# si4463.net
KiCad netlist of a schematic drawn in Altium Designer
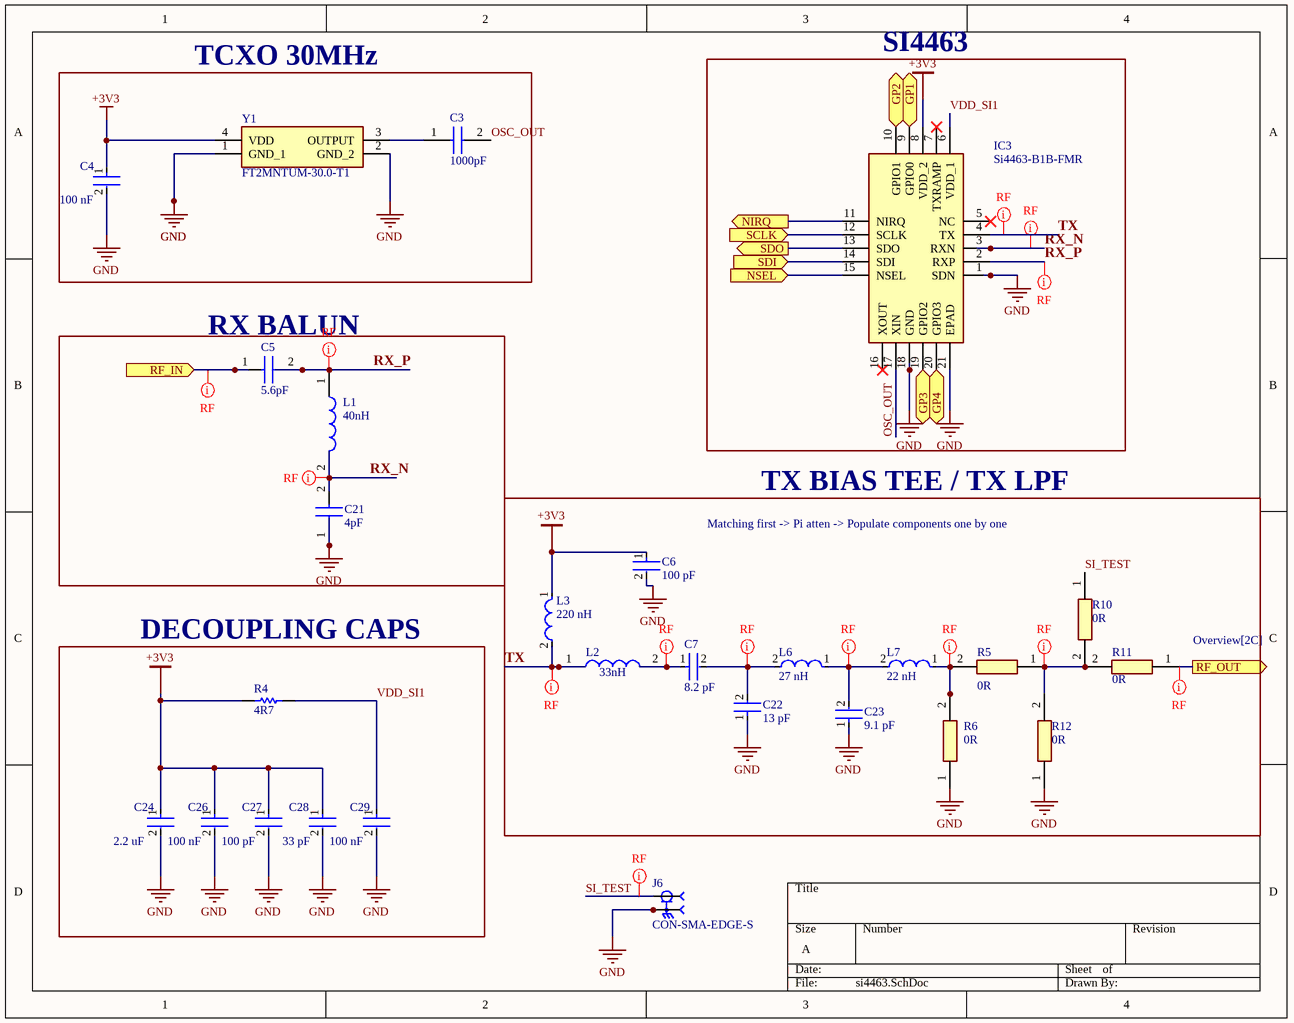
[diagram p0: si4463.SchDoc]

(export (version "E")
  (design (tool "Eeschema 10.0.6"))
  (components
    (comp (ref "C3")
      (value "1000pF")
      (footprint "SamacSys:C0402")
      (description "C0402C102K5RAC-TU")
      (libsource (lib "*") (part "C0402C102K5RAC-TU"))
    )
    (comp (ref "C4")
      (value "100 nF")
      (footprint "FP-GCM155-0_05-IPC_C")
      (description "Ceramic Capacitor for Automotive 100nF ±10% 16VDC X7R 0402 Paper T/R Name: GCM155R71C104KA55D")
      (fields (field (name "VOLTAGE") "16V") (field (name "TOLERANCE") "10%"))
      (libsource (lib "Altium Content Vault") (part "02cd4be3c70576c341d710602a673aa"))
    )
    (comp (ref "C5")
      (value "5.6pF")
      (footprint "SamacSys:CAPC1005X55N")
      (description "GJM1555C1H5R6BB01D")
      (fields (field (name "MOUSER PART NUMBER") "81-GJM1555C1H5R6BB1D"))
      (libsource (lib "*") (part "GJM1555C1H5R6BB01D"))
    )
    (comp (ref "C6")
      (value "100 pF")
      (footprint "FP-GQM187-0_15-MFG")
      (description "Ceramic Capacitor 100pF ±5% 250VDC C0G 0603 Paper T/R Name: GQM1875C2E101JB12D")
      (fields (field (name "TOLERANCE") "5%"))
      (libsource (lib "Altium Content Vault") (part "02cd4be3c70576c341d710602a673aa"))
    )
    (comp (ref "C7")
      (value "8.2 pF")
      (footprint "FP-GJM155-0_05-MFG")
      (description "Multi-Layer Ceramic Capacitor 8.2pF C0G  ±0.05pF 0402 Paper T/R")
      (libsource (lib "Altium Content Vault") (part "02cd4be3c70576c341d710602a673aa"))
    )
    (comp (ref "C21")
      (value "4pF")
      (footprint "SamacSys:CAPC1005X55N")
      (description "GJM1555C1H4R0BB01D")
      (fields (field (name "MOUSER PART NUMBER") "81-GJM1555C1H4R0BB01"))
      (libsource (lib "*") (part "GJM1555C1H4R0BB01D"))
    )
    (comp (ref "C22")
      (value "13 pF")
      (footprint "FP-GJM155-0_05-IPC_B")
      (description "Multi-Layer Ceramic Capacitor 13pF C0G  ±2% 0402 Paper T/R Name: GJM1555C1H130GB01D")
      (fields (field (name "TOLERANCE") "2%"))
      (libsource (lib "Altium Content Vault") (part "02cd4be3c70576c341d710602a673aa"))
    )
    (comp (ref "C23")
      (value "9.1 pF")
      (footprint "FP-GJM155-0_05-IPC_B")
      (description "Multi-Layer Ceramic Capacitor 9.1pF C0G  ±0.1pF 0402 Paper T/R Name: GJM1555C1H9R1BB01D")
      (libsource (lib "Altium Content Vault") (part "02cd4be3c70576c341d710602a673aa"))
    )
    (comp (ref "C24")
      (value "2.2 uF")
      (footprint "FP-GRM155-0_2-IPC_A")
      (fields (field (name "TOLERANCE") "10%"))
      (libsource (lib "Altium Content Vault") (part "b4654b650e69147ec39a6b967a45e02"))
    )
    (comp (ref "C26")
      (value "100 nF")
      (footprint "FP-GCM155-0_05-IPC_C")
      (description "Ceramic Capacitor for Automotive 100nF ±10% 16VDC X7R 0402 Paper T/R Name: GCM155R71C104KA55D")
      (fields (field (name "VOLTAGE") "16V") (field (name "TOLERANCE") "10%"))
      (libsource (lib "Altium Content Vault") (part "02cd4be3c70576c341d710602a673aa"))
    )
    (comp (ref "C27")
      (value "100 pF")
      (footprint "FP-GQM187-0_15-MFG")
      (description "Ceramic Capacitor 100pF ±5% 250VDC C0G 0603 Paper T/R Name: GQM1875C2E101JB12D")
      (fields (field (name "TOLERANCE") "5%"))
      (libsource (lib "Altium Content Vault") (part "02cd4be3c70576c341d710602a673aa"))
    )
    (comp (ref "C28")
      (value "33 pF")
      (footprint "FP-GJM155-0_05-MFG")
      (description "Multi-Layer Ceramic Capacitor 33pF C0G  ±5% 0402 Paper T/R Name: GJM1555C1H330JB01D")
      (fields (field (name "TOLERANCE") "5%"))
      (libsource (lib "Altium Content Vault") (part "02cd4be3c70576c341d710602a673aa"))
    )
    (comp (ref "C29")
      (value "100 nF")
      (footprint "FP-GCM155-0_05-IPC_C")
      (description "Ceramic Capacitor for Automotive 100nF ±10% 16VDC X7R 0402 Paper T/R Name: GCM155R71C104KA55D")
      (fields (field (name "VOLTAGE") "16V") (field (name "TOLERANCE") "10%"))
      (libsource (lib "Altium Content Vault") (part "02cd4be3c70576c341d710602a673aa"))
    )
    (comp (ref "IC3")
      (value "Si4463-B1B-FMR")
      (footprint "SamacSys:QFN50P400X400X90-21N-D")
      (description "Integrated Circuit")
      (fields
        (field (name "MOUSER PART NUMBER") "634-SI4463-B1B-FMR")
        (field (name "ARROW PART NUMBER") "SI4463-B1B-FMR")
      )
      (libsource (lib "*") (part "Si4463-B1B-FMR"))
    )
    (comp (ref "J6")
      (value "CON-SMA-EDGE-S")
      (footprint "RFSOLUTIONS_CON-SMA-EDGE-S")
      (description "SMA Connector Jack, Female Socket - Board Edge, End Launch Solder")
      (fields (field (name "MF") "RF Solutions") (field (name "DIGI-KEY_PART_NUMBER") "CON-SMA-EDGE-S-ND"))
      (libsource (lib "Americas- Calgary to Space- Calgary University") (part "CON-SMA-EDGE-S"))
    )
    (comp (ref "L1")
      (value "40nH")
      (footprint "SamacSys:LQW15CNR20J00B")
      (description "LQW15AN40NJ00D")
      (fields (field (name "MOUSER PART NUMBER") "81-LQW15AN40NJ00D"))
      (libsource (lib "*") (part "LQW15AN40NJ00D"))
    )
    (comp (ref "L2")
      (value "33nH")
      (footprint "SamacSys:LQW15CNR20J00B")
      (description "LQW15AN33NJ00D")
      (fields (field (name "MOUSER PART NUMBER") "81-LQW15AN33NJ00D"))
      (libsource (lib "*") (part "LQW15AN33NJ00D"))
    )
    (comp (ref "L3")
      (value "220 nH")
      (footprint "FP-LQW18AN_80-MFG")
      (description "Wire Wound RF Inductor for Automotive 220nH ±5% 280mA 2.08Ω 0603 (1608) Name: LQW18ANR22J8ZD")
      (libsource (lib "Altium Content Vault") (part "725321dda6339637d4d059423bc1c3c"))
    )
    (comp (ref "L6")
      (value "27 nH")
      (footprint "FP-LQW15AN_00-W0_5-0_1-MFG")
      (description "Wire Wound RF Inductor 27nH ±3% 280mA 0.52Ω 0402 (1005) Name: LQW15AN27NH00D")
      (fields (field (name "TOLERANCE") "3%"))
      (libsource (lib "Altium Content Vault") (part "725321dda6339637d4d059423bc1c3c"))
    )
    (comp (ref "L7")
      (value "22 nH")
      (footprint "FP-LQW15AN_00-W0_6-0_1-MFG")
      (description "Wire Wound RF Inductor 22nH ±3% 310mA 0.3Ω 0402 (1005) Name: LQW15AN22NH00D")
      (fields (field (name "TOLERANCE") "3%"))
      (libsource (lib "Altium Content Vault") (part "725321dda6339637d4d059423bc1c3c"))
    )
    (comp (ref "R4")
      (value "4R7")
      (footprint "RESC3216X65X100LL20T15")
      (description "Name: RL1632R-4R70-F")
      (fields (field (name "MANUFACTURER") "Susumu") (field (name "PART NUMBER") "RL1632R-4R70-F"))
      (libsource (lib "Altium Content Vault") (part "RES"))
    )
    (comp (ref "R5")
      (value "0R")
      (footprint "SamacSys:RESC1608X55N")
      (description "RC0603JR-070RL")
      (fields (field (name "MOUSER PART NUMBER") "603-RC0603JR-070RL"))
      (libsource (lib "*") (part "RC0603JR-070RL"))
    )
    (comp (ref "R6")
      (value "0R")
      (footprint "SamacSys:RESC1608X55N")
      (description "RC0603JR-070RL")
      (fields (field (name "MOUSER PART NUMBER") "603-RC0603JR-070RL"))
      (libsource (lib "") (part "RC0603JR-070RL_1"))
    )
    (comp (ref "R10")
      (value "0R")
      (footprint "SamacSys:RESC1005X40N")
      (description "RC0402JR-070RL")
      (fields (field (name "MOUSER PART NUMBER") "603-RC0402JR-070RL"))
      (libsource (lib "*") (part "RC0402JR-070RL"))
    )
    (comp (ref "R11")
      (value "0R")
      (footprint "SamacSys:RESC1608X55N")
      (description "RC0603JR-070RL")
      (fields (field (name "MOUSER PART NUMBER") "603-RC0603JR-070RL"))
      (libsource (lib "*") (part "RC0603JR-070RL"))
    )
    (comp (ref "R12")
      (value "0R")
      (footprint "SamacSys:RESC1608X55N")
      (description "RC0603JR-070RL")
      (fields (field (name "MOUSER PART NUMBER") "603-RC0603JR-070RL"))
      (libsource (lib "") (part "RC0603JR-070RL_1"))
    )
    (comp (ref "Y1")
      (value "FT2MNTUM-30.0-T1")
      (footprint "SamacSys:FT2MNTUM300T1")
      (description "Crystal or Oscillator")
      (fields (field (name "MOUSER PART NUMBER") "815-FT2MNTUM-30.0-T1"))
      (libsource (lib "*") (part "FT2MNTUM-30.0-T1"))
    )
  )
  (nets
    (net (code "1") (name "+3V3") (class "Default")
      (node (ref "C24") (pin "1") (pinfunction "1_1") (pintype "passive"))
      (node (ref "C26") (pin "1") (pinfunction "1_1") (pintype "passive"))
      (node (ref "C27") (pin "1") (pinfunction "1_1") (pintype "passive"))
      (node (ref "C28") (pin "1") (pinfunction "1_1") (pintype "passive"))
      (node (ref "C4") (pin "1") (pinfunction "1_1") (pintype "passive"))
      (node (ref "C6") (pin "1") (pinfunction "1_1") (pintype "passive"))
      (node (ref "IC3") (pin "8") (pinfunction "VDD_2_8") (pintype "passive"))
      (node (ref "L3") (pin "1") (pinfunction "1_1") (pintype "passive"))
      (node (ref "R4") (pin "1") (pinfunction "1_1") (pintype "passive"))
      (node (ref "Y1") (pin "4") (pinfunction "VDD_4") (pintype "passive"))
    )
    (net (code "2") (name "/GP1") (class "Default")
      (node (ref "IC3") (pin "9") (pinfunction "GPIO0_9") (pintype "passive"))
    )
    (net (code "3") (name "/GP2") (class "Default")
      (node (ref "IC3") (pin "10") (pinfunction "GPIO1_10") (pintype "passive"))
    )
    (net (code "4") (name "/GP3") (class "Default")
      (node (ref "IC3") (pin "19") (pinfunction "GPIO2_19") (pintype "passive"))
    )
    (net (code "5") (name "/GP4") (class "Default")
      (node (ref "IC3") (pin "20") (pinfunction "GPIO3_20") (pintype "passive"))
    )
    (net (code "6") (name "/NIRQ") (class "Default")
      (node (ref "IC3") (pin "11") (pinfunction "NIRQ_11") (pintype "passive"))
    )
    (net (code "7") (name "/NSEL") (class "Default")
      (node (ref "IC3") (pin "15") (pinfunction "NSEL_15") (pintype "passive"))
    )
    (net (code "8") (name "/OSC_OUT") (class "Default")
      (node (ref "C3") (pin "2") (pinfunction "2_2") (pintype "passive"))
      (node (ref "IC3") (pin "17") (pinfunction "XIN_17") (pintype "passive"))
    )
    (net (code "9") (name "/RF_IN") (class "Default")
      (node (ref "C5") (pin "1") (pinfunction "1_1") (pintype "passive"))
    )
    (net (code "10") (name "/RF_OUT") (class "Default")
      (node (ref "R11") (pin "1") (pinfunction "1_1") (pintype "passive"))
    )
    (net (code "11") (name "/RX_N") (class "Default")
      (node (ref "C21") (pin "2") (pinfunction "2_2") (pintype "passive"))
      (node (ref "IC3") (pin "3") (pinfunction "RXN_3") (pintype "passive"))
      (node (ref "L1") (pin "2") (pinfunction "2_2") (pintype "passive"))
    )
    (net (code "12") (name "/RX_P") (class "Default")
      (node (ref "C5") (pin "2") (pinfunction "2_2") (pintype "passive"))
      (node (ref "IC3") (pin "2") (pinfunction "RXP_2") (pintype "passive"))
      (node (ref "L1") (pin "1") (pinfunction "1_1") (pintype "passive"))
    )
    (net (code "13") (name "/SCLK") (class "Default")
      (node (ref "IC3") (pin "12") (pinfunction "SCLK_12") (pintype "passive"))
    )
    (net (code "14") (name "/SDI") (class "Default")
      (node (ref "IC3") (pin "14") (pinfunction "SDI_14") (pintype "passive"))
    )
    (net (code "15") (name "/SDO") (class "Default")
      (node (ref "IC3") (pin "13") (pinfunction "SDO_13") (pintype "passive"))
    )
    (net (code "16") (name "/SI_TEST") (class "Default")
      (node (ref "J6") (pin "1") (pinfunction "1_1") (pintype "passive"))
      (node (ref "R10") (pin "1") (pinfunction "1_1") (pintype "passive"))
    )
    (net (code "17") (name "/TX") (class "Default")
      (node (ref "IC3") (pin "4") (pinfunction "TX_4") (pintype "passive"))
      (node (ref "L2") (pin "1") (pinfunction "1_1") (pintype "passive"))
      (node (ref "L3") (pin "2") (pinfunction "2_2") (pintype "passive"))
    )
    (net (code "18") (name "/VDD_SI1") (class "Default")
      (node (ref "C29") (pin "1") (pinfunction "1_1") (pintype "passive"))
      (node (ref "IC3") (pin "6") (pinfunction "VDD_1_6") (pintype "passive"))
      (node (ref "R4") (pin "2") (pinfunction "2_2") (pintype "passive"))
    )
    (net (code "19") (name "GND") (class "Default")
      (node (ref "C21") (pin "1") (pinfunction "1_1") (pintype "passive"))
      (node (ref "C22") (pin "1") (pinfunction "1_1") (pintype "passive"))
      (node (ref "C23") (pin "1") (pinfunction "1_1") (pintype "passive"))
      (node (ref "C24") (pin "2") (pinfunction "2_2") (pintype "passive"))
      (node (ref "C26") (pin "2") (pinfunction "2_2") (pintype "passive"))
      (node (ref "C27") (pin "2") (pinfunction "2_2") (pintype "passive"))
      (node (ref "C28") (pin "2") (pinfunction "2_2") (pintype "passive"))
      (node (ref "C29") (pin "2") (pinfunction "2_2") (pintype "passive"))
      (node (ref "C4") (pin "2") (pinfunction "2_2") (pintype "passive"))
      (node (ref "C6") (pin "2") (pinfunction "2_2") (pintype "passive"))
      (node (ref "IC3") (pin "1") (pinfunction "SDN_1") (pintype "passive"))
      (node (ref "IC3") (pin "18") (pinfunction "GND_18") (pintype "passive"))
      (node (ref "IC3") (pin "21") (pinfunction "EPAD_21") (pintype "passive"))
      (node (ref "J6") (pin "G1") (pinfunction "2_G1") (pintype "passive"))
      (node (ref "J6") (pin "G2") (pinfunction "2_G2") (pintype "passive"))
      (node (ref "J6") (pin "G3") (pinfunction "2_G3") (pintype "passive"))
      (node (ref "J6") (pin "G4") (pinfunction "2_G4") (pintype "passive"))
      (node (ref "R12") (pin "1") (pinfunction "1_1") (pintype "passive"))
      (node (ref "R6") (pin "1") (pinfunction "1_1") (pintype "passive"))
      (node (ref "Y1") (pin "1") (pinfunction "GND_1_1") (pintype "passive"))
      (node (ref "Y1") (pin "2") (pinfunction "GND_2_2") (pintype "passive"))
    )
    (net (code "20") (name "Net-(C7-Pad1)") (class "Default")
      (node (ref "C7") (pin "1") (pinfunction "1_1") (pintype "passive"))
      (node (ref "L2") (pin "2") (pinfunction "2_2") (pintype "passive"))
    )
    (net (code "21") (name "Net-(C22-Pad2)") (class "Default")
      (node (ref "C22") (pin "2") (pinfunction "2_2") (pintype "passive"))
      (node (ref "C7") (pin "2") (pinfunction "2_2") (pintype "passive"))
      (node (ref "L6") (pin "2") (pinfunction "2_2") (pintype "passive"))
    )
    (net (code "22") (name "Net-(C23-Pad2)") (class "Default")
      (node (ref "C23") (pin "2") (pinfunction "2_2") (pintype "passive"))
      (node (ref "L6") (pin "1") (pinfunction "1_1") (pintype "passive"))
      (node (ref "L7") (pin "2") (pinfunction "2_2") (pintype "passive"))
    )
    (net (code "23") (name "Net-(L7-Pad1)") (class "Default")
      (node (ref "L7") (pin "1") (pinfunction "1_1") (pintype "passive"))
      (node (ref "R5") (pin "2") (pinfunction "2_2") (pintype "passive"))
      (node (ref "R6") (pin "2") (pinfunction "2_2") (pintype "passive"))
    )
    (net (code "24") (name "Net-(R10-Pad2)") (class "Default")
      (node (ref "R10") (pin "2") (pinfunction "2_2") (pintype "passive"))
      (node (ref "R11") (pin "2") (pinfunction "2_2") (pintype "passive"))
      (node (ref "R12") (pin "2") (pinfunction "2_2") (pintype "passive"))
      (node (ref "R5") (pin "1") (pinfunction "1_1") (pintype "passive"))
    )
    (net (code "25") (name "Net-(Y1-OUTPUT)") (class "Default")
      (node (ref "C3") (pin "1") (pinfunction "1_1") (pintype "passive"))
      (node (ref "Y1") (pin "3") (pinfunction "OUTPUT_3") (pintype "passive"))
    )
    (net (code "26") (name "unconnected-(IC3-NC-Pad5)") (class "Default")
      (node (ref "IC3") (pin "5") (pinfunction "NC_5") (pintype "passive+no_connect"))
    )
    (net (code "27") (name "unconnected-(IC3-TXRAMP-Pad7)") (class "Default")
      (node (ref "IC3") (pin "7") (pinfunction "TXRAMP_7") (pintype "passive+no_connect"))
    )
    (net (code "28") (name "unconnected-(IC3-XOUT-Pad16)") (class "Default")
      (node (ref "IC3") (pin "16") (pinfunction "XOUT_16") (pintype "passive+no_connect"))
    )
  )
)
